# WiFi_Board_R1.net
KiCad netlist of a schematic drawn in EAGLE
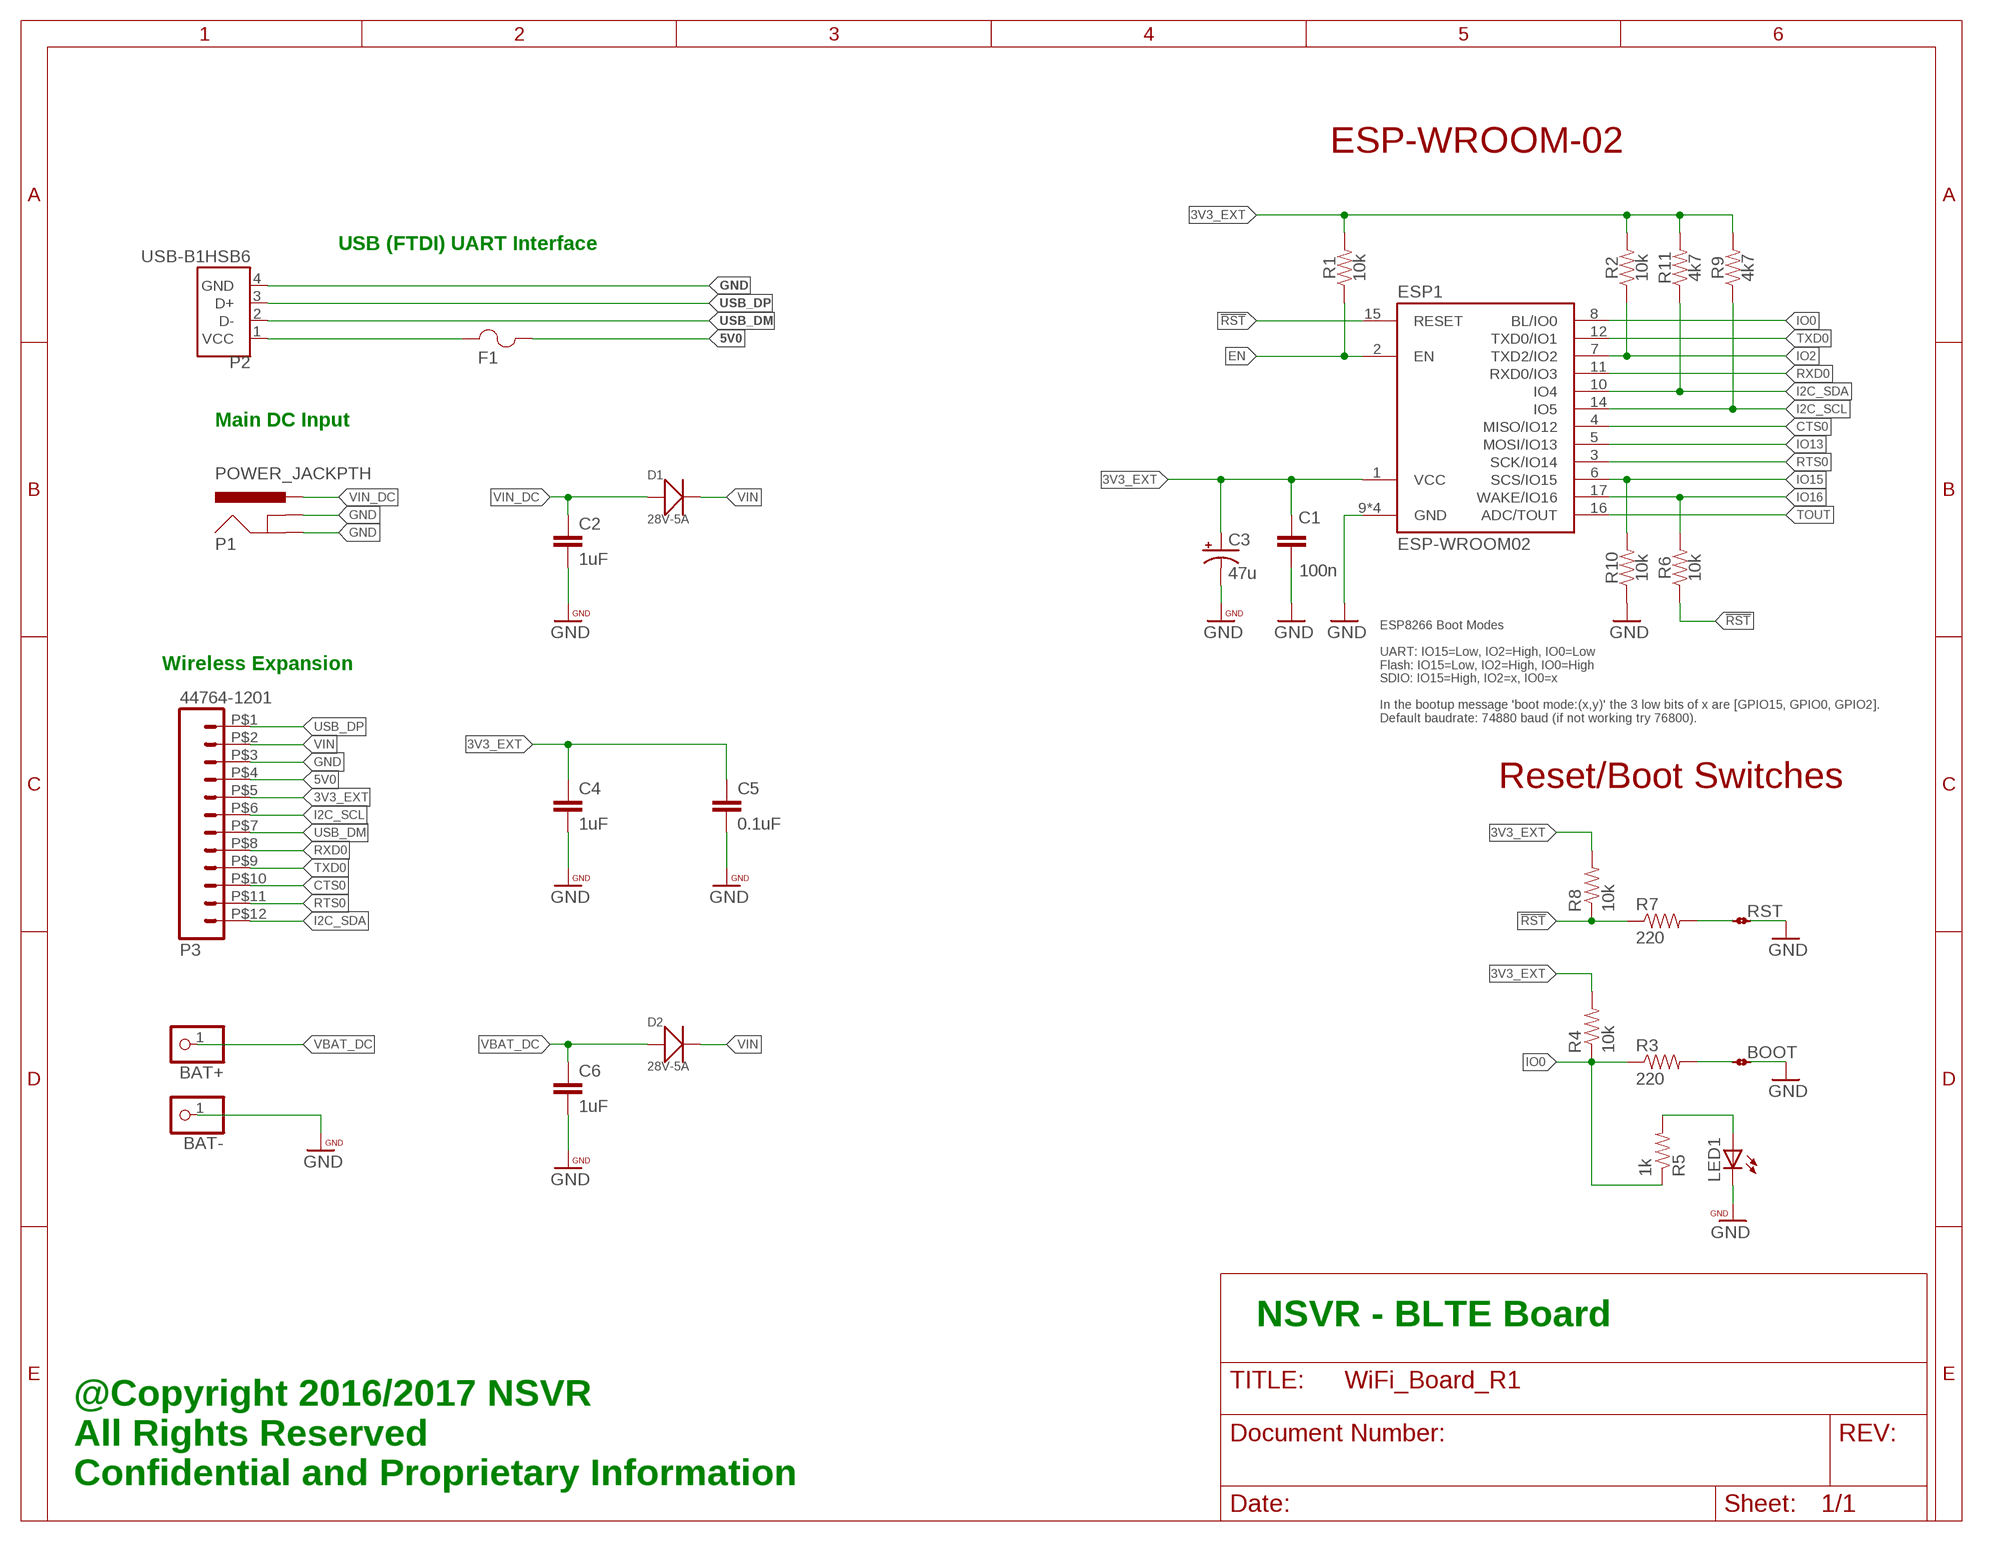
[diagram p0: schematic, sheet 1]

(export (version "E")
  (design (tool "Eeschema 10.0.6"))
  (components
    (comp (ref "BAT+")
      (value "WPAD-1-PTH")
      (footprint "eagle-import:WPAD-1-PTH-2.54")
      (libsource (lib "eagle-import") (part "WPAD-1-PTH"))
    )
    (comp (ref "BAT-")
      (value "WPAD-1-PTH")
      (footprint "eagle-import:WPAD-1-PTH-2.54")
      (libsource (lib "eagle-import") (part "WPAD-1-PTH"))
    )
    (comp (ref "BOOT")
      (value "JMP-2-NO-PTH")
      (footprint "eagle-import:JMP-2-NO-PTH-2.54")
      (libsource (lib "eagle-import") (part "JMP-2-NO-PTH"))
    )
    (comp (ref "C1")
      (value "100n")
      (footprint "eagle-import:0402-CAP")
      (libsource (lib "eagle-import") (part "CAP0402-CAP"))
    )
    (comp (ref "C2")
      (value "1uF")
      (footprint "eagle-import:0402-CAP")
      (libsource (lib "eagle-import") (part "CAP0402-CAP"))
    )
    (comp (ref "C3")
      (value "47u")
      (footprint "eagle-import:PANASONIC_D")
      (libsource (lib "eagle-import") (part "CAP_POLD"))
    )
    (comp (ref "C4")
      (value "1uF")
      (footprint "eagle-import:0402-CAP")
      (libsource (lib "eagle-import") (part "CAP0402-CAP"))
    )
    (comp (ref "C5")
      (value "0.1uF")
      (footprint "eagle-import:0402-CAP")
      (libsource (lib "eagle-import") (part "CAP0402-CAP"))
    )
    (comp (ref "C6")
      (value "1uF")
      (footprint "eagle-import:0402-CAP")
      (libsource (lib "eagle-import") (part "CAP0402-CAP"))
    )
    (comp (ref "D1")
      (value "28V-5A")
      (footprint "eagle-import:DO-214AA")
      (fields (field (name "MPN") "SS54B"))
      (libsource (lib "eagle-import") (part "SMD-DIODE-SCHOTTKY-28V-5A(DO-214AA)"))
    )
    (comp (ref "D2")
      (value "28V-5A")
      (footprint "eagle-import:DO-214AA")
      (fields (field (name "MPN") "SS54B"))
      (libsource (lib "eagle-import") (part "SMD-DIODE-SCHOTTKY-28V-5A(DO-214AA)"))
    )
    (comp (ref "ESP1")
      (value "ESP-WROOM02")
      (footprint "eagle-import:ESP-WROOM02")
      (libsource (lib "eagle-import") (part "ESP-WROOM02"))
    )
    (comp (ref "F1")
      (value "1206L050YR")
      (footprint "eagle-import:1206LSERIES")
      (fields (field (name "COPYRIGHT") "Copyright C 2015 Accelerated Designs. All rights reserved"))
      (libsource (lib "eagle-import") (part "1206L050YR"))
    )
    (comp (ref "LED1")
      (value "LEDCHIP-LED0603")
      (footprint "eagle-import:CHIP-LED0603")
      (libsource (lib "eagle-import") (part "LEDCHIP-LED0603"))
    )
    (comp (ref "P1")
      (value "POWER_JACKPTH")
      (footprint "eagle-import:POWER_JACK_PTH")
      (libsource (lib "eagle-import") (part "POWER_JACKPTH"))
    )
    (comp (ref "P2")
      (value "USB-B1HSB6")
      (footprint "eagle-import:OST_USB-B1HSB6")
      (fields (field (name "MF") "On Shore Technology"))
      (libsource (lib "eagle-import") (part "USB-B1HSB6"))
    )
    (comp (ref "P3")
      (value "44764-1201")
      (footprint "eagle-import:44764-1201")
      (libsource (lib "eagle-import") (part "44764-1201"))
    )
    (comp (ref "R1")
      (value "10k")
      (footprint "eagle-import:EIA-0402")
      (libsource (lib "eagle-import") (part "RESISTOR0402-TYP"))
    )
    (comp (ref "R2")
      (value "10k")
      (footprint "eagle-import:EIA-0402")
      (libsource (lib "eagle-import") (part "RESISTOR0402-TYP"))
    )
    (comp (ref "R3")
      (value "220")
      (footprint "eagle-import:EIA-0402")
      (libsource (lib "eagle-import") (part "RESISTOR0402-TYP"))
    )
    (comp (ref "R4")
      (value "10k")
      (footprint "eagle-import:EIA-0402")
      (libsource (lib "eagle-import") (part "RESISTOR0402-TYP"))
    )
    (comp (ref "R5")
      (value "1k")
      (footprint "eagle-import:EIA-0402")
      (libsource (lib "eagle-import") (part "RESISTOR0402-TYP"))
    )
    (comp (ref "R6")
      (value "10k")
      (footprint "eagle-import:EIA-0402")
      (libsource (lib "eagle-import") (part "RESISTOR0402-TYP"))
    )
    (comp (ref "R7")
      (value "220")
      (footprint "eagle-import:EIA-0402")
      (libsource (lib "eagle-import") (part "RESISTOR0402-TYP"))
    )
    (comp (ref "R8")
      (value "10k")
      (footprint "eagle-import:EIA-0402")
      (libsource (lib "eagle-import") (part "RESISTOR0402-TYP"))
    )
    (comp (ref "R9")
      (value "4k7")
      (footprint "eagle-import:EIA-0402")
      (libsource (lib "eagle-import") (part "RESISTOR0402-TYP"))
    )
    (comp (ref "R10")
      (value "10k")
      (footprint "eagle-import:EIA-0402")
      (libsource (lib "eagle-import") (part "RESISTOR0402-TYP"))
    )
    (comp (ref "R11")
      (value "4k7")
      (footprint "eagle-import:EIA-0402")
      (libsource (lib "eagle-import") (part "RESISTOR0402-TYP"))
    )
    (comp (ref "RST")
      (value "JMP-2-NO-PTH")
      (footprint "eagle-import:JMP-2-NO-PTH-2.54")
      (libsource (lib "eagle-import") (part "JMP-2-NO-PTH"))
    )
  )
  (nets
    (net (code "1") (name "/~{RST}") (class "Default")
      (node (ref "ESP1") (pin "15") (pinfunction "RESET_15") (pintype "bidirectional"))
      (node (ref "R6") (pin "1") (pinfunction "1_1") (pintype "passive"))
      (node (ref "R7") (pin "1") (pinfunction "1_1") (pintype "passive"))
      (node (ref "R8") (pin "1") (pinfunction "1_1") (pintype "passive"))
    )
    (net (code "2") (name "3V3_EXT") (class "Default")
      (node (ref "C1") (pin "2") (pinfunction "2_2") (pintype "passive"))
      (node (ref "C3") (pin "+") (pinfunction "+_+") (pintype "passive"))
      (node (ref "C4") (pin "1") (pinfunction "1_1") (pintype "passive"))
      (node (ref "C5") (pin "1") (pinfunction "1_1") (pintype "passive"))
      (node (ref "ESP1") (pin "1") (pinfunction "VCC_1") (pintype "power_in"))
      (node (ref "P3") (pin "P$5") (pinfunction "5_P$5") (pintype "passive"))
      (node (ref "R1") (pin "2") (pinfunction "2_2") (pintype "passive"))
      (node (ref "R11") (pin "2") (pinfunction "2_2") (pintype "passive"))
      (node (ref "R2") (pin "2") (pinfunction "2_2") (pintype "passive"))
      (node (ref "R4") (pin "2") (pinfunction "2_2") (pintype "passive"))
      (node (ref "R8") (pin "2") (pinfunction "2_2") (pintype "passive"))
      (node (ref "R9") (pin "2") (pinfunction "2_2") (pintype "passive"))
    )
    (net (code "3") (name "5V0") (class "Default")
      (node (ref "F1") (pin "2") (pinfunction "2_2") (pintype "passive"))
      (node (ref "P3") (pin "P$4") (pinfunction "4_P$4") (pintype "passive"))
    )
    (net (code "4") (name "CTS0") (class "Default")
      (node (ref "ESP1") (pin "4") (pinfunction "MISO/IO12_4") (pintype "bidirectional"))
      (node (ref "P3") (pin "P$10") (pinfunction "10_P$10") (pintype "passive"))
    )
    (net (code "5") (name "EN") (class "Default")
      (node (ref "ESP1") (pin "2") (pinfunction "EN_2") (pintype "bidirectional"))
      (node (ref "R1") (pin "1") (pinfunction "1_1") (pintype "passive"))
    )
    (net (code "6") (name "GND") (class "Default")
      (node (ref "BAT-") (pin "1") (pinfunction "1_1") (pintype "passive"))
      (node (ref "BOOT") (pin "2") (pinfunction "2_2") (pintype "passive"))
      (node (ref "C1") (pin "1") (pinfunction "1_1") (pintype "passive"))
      (node (ref "C2") (pin "2") (pinfunction "2_2") (pintype "passive"))
      (node (ref "C3") (pin "-") (pinfunction "-_-") (pintype "passive"))
      (node (ref "C4") (pin "2") (pinfunction "2_2") (pintype "passive"))
      (node (ref "C5") (pin "2") (pinfunction "2_2") (pintype "passive"))
      (node (ref "C6") (pin "2") (pinfunction "2_2") (pintype "passive"))
      (node (ref "ESP1") (pin "13") (pinfunction "GND_13") (pintype "power_in"))
      (node (ref "ESP1") (pin "18") (pinfunction "GND_18") (pintype "power_in"))
      (node (ref "ESP1") (pin "9") (pinfunction "GND_9") (pintype "power_in"))
      (node (ref "ESP1") (pin "TP") (pinfunction "GND_TP") (pintype "power_in"))
      (node (ref "LED1") (pin "C") (pinfunction "C_C") (pintype "passive"))
      (node (ref "P1") (pin "GND") (pinfunction "GND_GND") (pintype "bidirectional"))
      (node (ref "P1") (pin "GNDBREAK") (pinfunction "GNDBREAK_GNDBREAK") (pintype "bidirectional"))
      (node (ref "P2") (pin "4") (pinfunction "GND_4") (pintype "power_in"))
      (node (ref "P3") (pin "P$3") (pinfunction "3_P$3") (pintype "passive"))
      (node (ref "R10") (pin "1") (pinfunction "1_1") (pintype "passive"))
      (node (ref "RST") (pin "2") (pinfunction "2_2") (pintype "passive"))
    )
    (net (code "7") (name "I2C_SCL") (class "Default")
      (node (ref "ESP1") (pin "14") (pinfunction "IO5_14") (pintype "bidirectional"))
      (node (ref "P3") (pin "P$6") (pinfunction "6_P$6") (pintype "passive"))
      (node (ref "R9") (pin "1") (pinfunction "1_1") (pintype "passive"))
    )
    (net (code "8") (name "I2C_SDA") (class "Default")
      (node (ref "ESP1") (pin "10") (pinfunction "IO4_10") (pintype "bidirectional"))
      (node (ref "P3") (pin "P$12") (pinfunction "12_P$12") (pintype "passive"))
      (node (ref "R11") (pin "1") (pinfunction "1_1") (pintype "passive"))
    )
    (net (code "9") (name "IO0") (class "Default")
      (node (ref "ESP1") (pin "8") (pinfunction "BL/IO0_8") (pintype "bidirectional"))
      (node (ref "R3") (pin "1") (pinfunction "1_1") (pintype "passive"))
      (node (ref "R4") (pin "1") (pinfunction "1_1") (pintype "passive"))
      (node (ref "R5") (pin "1") (pinfunction "1_1") (pintype "passive"))
    )
    (net (code "10") (name "IO2") (class "Default")
      (node (ref "ESP1") (pin "7") (pinfunction "TXD2/IO2_7") (pintype "bidirectional"))
      (node (ref "R2") (pin "1") (pinfunction "1_1") (pintype "passive"))
    )
    (net (code "11") (name "IO13") (class "Default")
      (node (ref "ESP1") (pin "5") (pinfunction "MOSI/IO13_5") (pintype "bidirectional"))
    )
    (net (code "12") (name "IO15") (class "Default")
      (node (ref "ESP1") (pin "6") (pinfunction "SCS/IO15_6") (pintype "bidirectional"))
      (node (ref "R10") (pin "2") (pinfunction "2_2") (pintype "passive"))
    )
    (net (code "13") (name "IO16") (class "Default")
      (node (ref "ESP1") (pin "17") (pinfunction "WAKE/IO16_17") (pintype "bidirectional"))
      (node (ref "R6") (pin "2") (pinfunction "2_2") (pintype "passive"))
    )
    (net (code "14") (name "Net-(BOOT-Pad1)") (class "Default")
      (node (ref "BOOT") (pin "1") (pinfunction "1_1") (pintype "passive"))
      (node (ref "R3") (pin "2") (pinfunction "2_2") (pintype "passive"))
    )
    (net (code "15") (name "Net-(LED1-PadA)") (class "Default")
      (node (ref "LED1") (pin "A") (pinfunction "A_A") (pintype "passive"))
      (node (ref "R5") (pin "2") (pinfunction "2_2") (pintype "passive"))
    )
    (net (code "16") (name "Net-(P2-VCC)") (class "Default")
      (node (ref "F1") (pin "1") (pinfunction "1_1") (pintype "passive"))
      (node (ref "P2") (pin "1") (pinfunction "VCC_1") (pintype "power_in"))
    )
    (net (code "17") (name "Net-(R7-Pad2)") (class "Default")
      (node (ref "R7") (pin "2") (pinfunction "2_2") (pintype "passive"))
      (node (ref "RST") (pin "1") (pinfunction "1_1") (pintype "passive"))
    )
    (net (code "18") (name "RTS0") (class "Default")
      (node (ref "ESP1") (pin "3") (pinfunction "SCK/IO14_3") (pintype "bidirectional"))
      (node (ref "P3") (pin "P$11") (pinfunction "11_P$11") (pintype "passive"))
    )
    (net (code "19") (name "RXD0") (class "Default")
      (node (ref "ESP1") (pin "11") (pinfunction "RXD0/IO3_11") (pintype "bidirectional"))
      (node (ref "P3") (pin "P$8") (pinfunction "8_P$8") (pintype "passive"))
    )
    (net (code "20") (name "TOUT") (class "Default")
      (node (ref "ESP1") (pin "16") (pinfunction "ADC/TOUT_16") (pintype "bidirectional"))
    )
    (net (code "21") (name "TXD0") (class "Default")
      (node (ref "ESP1") (pin "12") (pinfunction "TXD0/IO1_12") (pintype "bidirectional"))
      (node (ref "P3") (pin "P$9") (pinfunction "9_P$9") (pintype "passive"))
    )
    (net (code "22") (name "USB_DM") (class "Default")
      (node (ref "P2") (pin "2") (pinfunction "D-_2") (pintype "bidirectional"))
      (node (ref "P3") (pin "P$7") (pinfunction "7_P$7") (pintype "passive"))
    )
    (net (code "23") (name "USB_DP") (class "Default")
      (node (ref "P2") (pin "3") (pinfunction "D+_3") (pintype "bidirectional"))
      (node (ref "P3") (pin "P$1") (pinfunction "1_P$1") (pintype "passive"))
    )
    (net (code "24") (name "VBAT_DC") (class "Default")
      (node (ref "BAT+") (pin "1") (pinfunction "1_1") (pintype "passive"))
      (node (ref "C6") (pin "1") (pinfunction "1_1") (pintype "passive"))
      (node (ref "D2") (pin "+") (pinfunction "+_+") (pintype "passive"))
    )
    (net (code "25") (name "VIN") (class "Default")
      (node (ref "D1") (pin "-") (pinfunction "-_-") (pintype "passive"))
      (node (ref "D2") (pin "-") (pinfunction "-_-") (pintype "passive"))
      (node (ref "P3") (pin "P$2") (pinfunction "2_P$2") (pintype "passive"))
    )
    (net (code "26") (name "VIN_DC") (class "Default")
      (node (ref "C2") (pin "1") (pinfunction "1_1") (pintype "passive"))
      (node (ref "D1") (pin "+") (pinfunction "+_+") (pintype "passive"))
      (node (ref "P1") (pin "PWR") (pinfunction "PWR_PWR") (pintype "bidirectional"))
    )
  )
)
